# RLY.net
KiCad netlist of a schematic drawn in Altium Designer
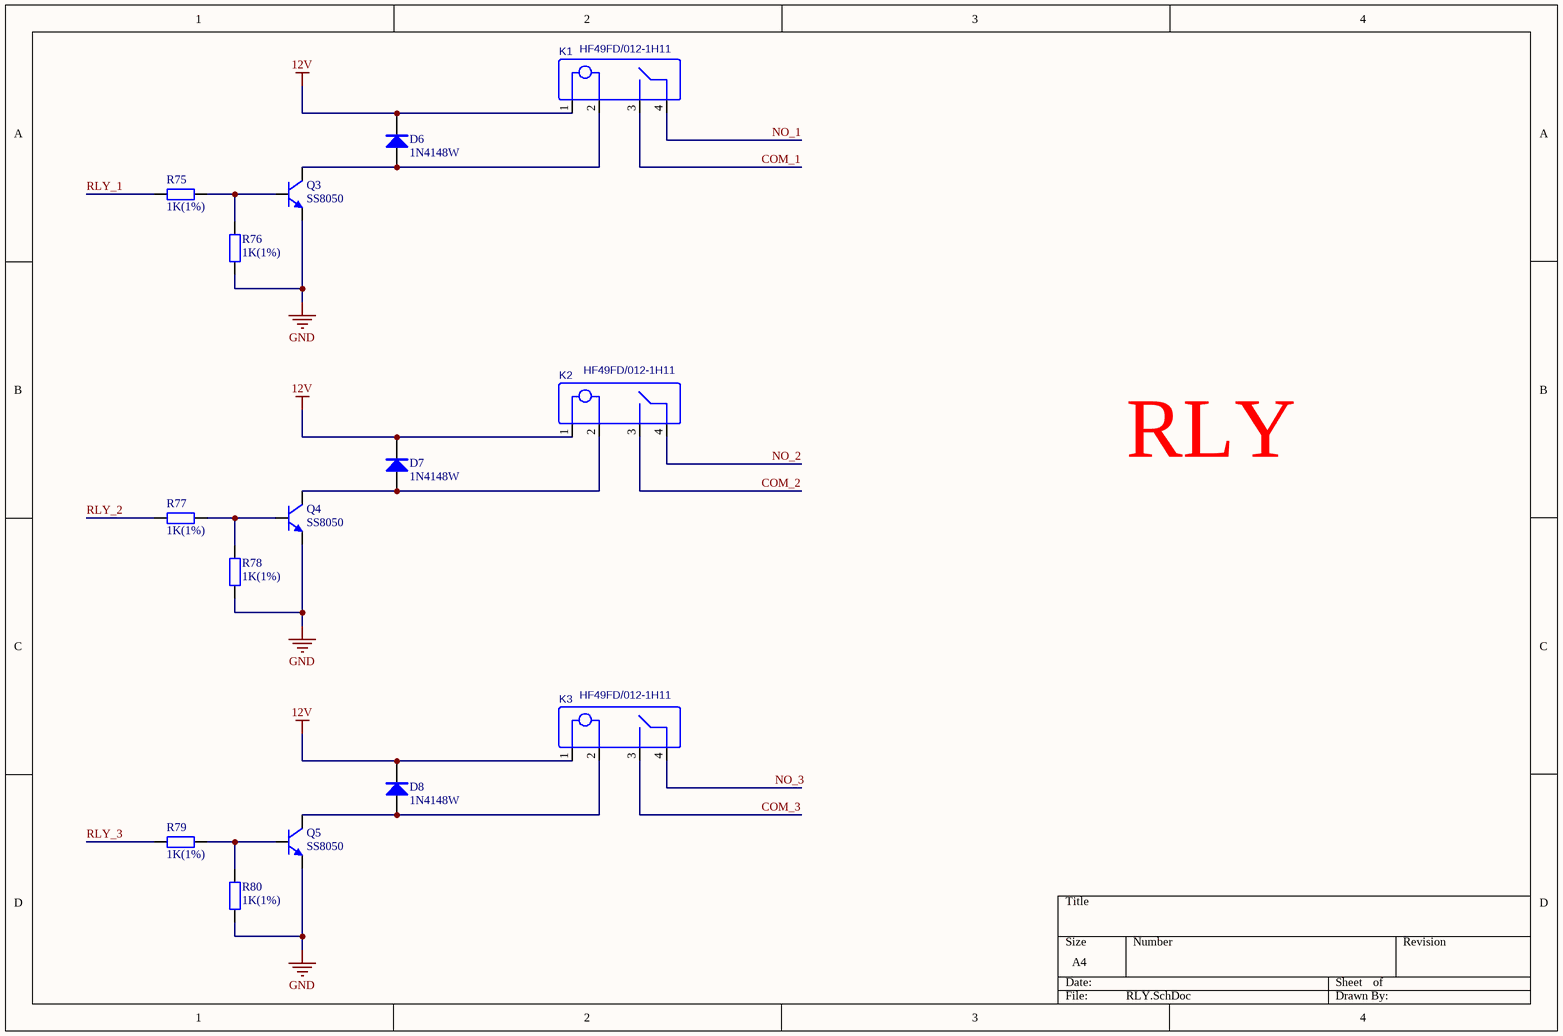
[diagram p0: RLY.SchDoc]

(export (version "E")
  (design (tool "Eeschema 10.0.6"))
  (components
    (comp (ref "D6")
      (value "1N4148W")
      (footprint "SOD-123")
      (description "高速开关二极管")
      (fields (field (name "版权归属") "源创客"))
      (libsource (lib "二极管-整流桥") (part "1N4148"))
    )
    (comp (ref "D7")
      (value "1N4148W")
      (footprint "SOD-123")
      (description "高速开关二极管")
      (fields (field (name "版权归属") "源创客"))
      (libsource (lib "二极管-整流桥") (part "1N4148"))
    )
    (comp (ref "D8")
      (value "1N4148W")
      (footprint "SOD-123")
      (description "高速开关二极管")
      (fields (field (name "版权归属") "源创客"))
      (libsource (lib "二极管-整流桥") (part "1N4148"))
    )
    (comp (ref "K1")
      (value "HF49FD/012-1H11")
      (footprint "RELAY-TH_HF49FD-XXX-1H11-XXX")
      (fields
        (field (name "BOM_SUPPLIER PART") "C399491")
        (field (name "BOM_MANUFACTURER PART") "HF49FD/012-1H12")
        (field (name "CONTRIBUTOR") "LCSC")
      )
      (libsource (lib "MICB") (part "HF49FD/012-1H11"))
    )
    (comp (ref "K2")
      (value "HF49FD/012-1H11")
      (footprint "RELAY-TH_HF49FD-XXX-1H11-XXX")
      (fields
        (field (name "BOM_SUPPLIER PART") "C399491")
        (field (name "BOM_MANUFACTURER PART") "HF49FD/012-1H12")
        (field (name "CONTRIBUTOR") "LCSC")
      )
      (libsource (lib "MICB") (part "HF49FD/012-1H11"))
    )
    (comp (ref "K3")
      (value "HF49FD/012-1H11")
      (footprint "RELAY-TH_HF49FD-XXX-1H11-XXX")
      (fields
        (field (name "BOM_SUPPLIER PART") "C399491")
        (field (name "BOM_MANUFACTURER PART") "HF49FD/012-1H12")
        (field (name "CONTRIBUTOR") "LCSC")
      )
      (libsource (lib "MICB") (part "HF49FD/012-1H11"))
    )
    (comp (ref "Q3")
      (value "SS8050")
      (footprint "SOT23-3N")
      (description "高频放大-NPN型")
      (fields (field (name "版权归属") "源创客"))
      (libsource (lib "三极管") (part "8050-SMD"))
    )
    (comp (ref "Q4")
      (value "SS8050")
      (footprint "SOT23-3N")
      (description "高频放大-NPN型")
      (fields (field (name "版权归属") "源创客"))
      (libsource (lib "三极管") (part "8050-SMD"))
    )
    (comp (ref "Q5")
      (value "SS8050")
      (footprint "SOT23-3N")
      (description "高频放大-NPN型")
      (fields (field (name "版权归属") "源创客"))
      (libsource (lib "三极管") (part "8050-SMD"))
    )
    (comp (ref "R75")
      (value "1K(1%)")
      (footprint "R 0603_L")
      (description "贴片电阻")
      (fields (field (name "版权归属") "源创客"))
      (libsource (lib "电阻-电容-电感") (part "R"))
    )
    (comp (ref "R76")
      (value "1K(1%)")
      (footprint "R 0603_L")
      (description "贴片电阻")
      (fields (field (name "版权归属") "源创客"))
      (libsource (lib "电阻-电容-电感") (part "R"))
    )
    (comp (ref "R77")
      (value "1K(1%)")
      (footprint "R 0603_L")
      (description "贴片电阻")
      (fields (field (name "版权归属") "源创客"))
      (libsource (lib "电阻-电容-电感") (part "R"))
    )
    (comp (ref "R78")
      (value "1K(1%)")
      (footprint "R 0603_L")
      (description "贴片电阻")
      (fields (field (name "版权归属") "源创客"))
      (libsource (lib "电阻-电容-电感") (part "R"))
    )
    (comp (ref "R79")
      (value "1K(1%)")
      (footprint "R 0603_L")
      (description "贴片电阻")
      (fields (field (name "版权归属") "源创客"))
      (libsource (lib "电阻-电容-电感") (part "R"))
    )
    (comp (ref "R80")
      (value "1K(1%)")
      (footprint "R 0603_L")
      (description "贴片电阻")
      (fields (field (name "版权归属") "源创客"))
      (libsource (lib "电阻-电容-电感") (part "R"))
    )
  )
  (nets
    (net (code "1") (name "/COM_1") (class "Default")
      (node (ref "K1") (pin "3") (pinfunction "3_3") (pintype "passive"))
    )
    (net (code "2") (name "/COM_2") (class "Default")
      (node (ref "K2") (pin "3") (pinfunction "3_3") (pintype "passive"))
    )
    (net (code "3") (name "/COM_3") (class "Default")
      (node (ref "K3") (pin "3") (pinfunction "3_3") (pintype "passive"))
    )
    (net (code "4") (name "/NO_1") (class "Default")
      (node (ref "K1") (pin "4") (pinfunction "4_4") (pintype "passive"))
    )
    (net (code "5") (name "/NO_2") (class "Default")
      (node (ref "K2") (pin "4") (pinfunction "4_4") (pintype "passive"))
    )
    (net (code "6") (name "/NO_3") (class "Default")
      (node (ref "K3") (pin "4") (pinfunction "4_4") (pintype "passive"))
    )
    (net (code "7") (name "/RLY_1") (class "Default")
      (node (ref "R75") (pin "2") (pinfunction "2_2") (pintype "passive"))
    )
    (net (code "8") (name "/RLY_2") (class "Default")
      (node (ref "R77") (pin "2") (pinfunction "2_2") (pintype "passive"))
    )
    (net (code "9") (name "/RLY_3") (class "Default")
      (node (ref "R79") (pin "2") (pinfunction "2_2") (pintype "passive"))
    )
    (net (code "10") (name "12V") (class "Default")
      (node (ref "D6") (pin "2") (pinfunction "K_2") (pintype "passive"))
      (node (ref "D7") (pin "2") (pinfunction "K_2") (pintype "passive"))
      (node (ref "D8") (pin "2") (pinfunction "K_2") (pintype "passive"))
      (node (ref "K1") (pin "1") (pinfunction "1_1") (pintype "passive"))
      (node (ref "K2") (pin "1") (pinfunction "1_1") (pintype "passive"))
      (node (ref "K3") (pin "1") (pinfunction "1_1") (pintype "passive"))
    )
    (net (code "11") (name "GND") (class "Default")
      (node (ref "Q3") (pin "2") (pinfunction "E_2") (pintype "passive"))
      (node (ref "Q4") (pin "2") (pinfunction "E_2") (pintype "passive"))
      (node (ref "Q5") (pin "2") (pinfunction "E_2") (pintype "passive"))
      (node (ref "R76") (pin "1") (pinfunction "1_1") (pintype "passive"))
      (node (ref "R78") (pin "1") (pinfunction "1_1") (pintype "passive"))
      (node (ref "R80") (pin "1") (pinfunction "1_1") (pintype "passive"))
    )
    (net (code "12") (name "Net-(D6-A)") (class "Default")
      (node (ref "D6") (pin "1") (pinfunction "A_1") (pintype "passive"))
      (node (ref "K1") (pin "2") (pinfunction "2_2") (pintype "passive"))
      (node (ref "Q3") (pin "3") (pinfunction "C_3") (pintype "passive"))
    )
    (net (code "13") (name "Net-(D7-A)") (class "Default")
      (node (ref "D7") (pin "1") (pinfunction "A_1") (pintype "passive"))
      (node (ref "K2") (pin "2") (pinfunction "2_2") (pintype "passive"))
      (node (ref "Q4") (pin "3") (pinfunction "C_3") (pintype "passive"))
    )
    (net (code "14") (name "Net-(D8-A)") (class "Default")
      (node (ref "D8") (pin "1") (pinfunction "A_1") (pintype "passive"))
      (node (ref "K3") (pin "2") (pinfunction "2_2") (pintype "passive"))
      (node (ref "Q5") (pin "3") (pinfunction "C_3") (pintype "passive"))
    )
    (net (code "15") (name "Net-(Q3-B)") (class "Default")
      (node (ref "Q3") (pin "1") (pinfunction "B_1") (pintype "passive"))
      (node (ref "R75") (pin "1") (pinfunction "1_1") (pintype "passive"))
      (node (ref "R76") (pin "2") (pinfunction "2_2") (pintype "passive"))
    )
    (net (code "16") (name "Net-(Q4-B)") (class "Default")
      (node (ref "Q4") (pin "1") (pinfunction "B_1") (pintype "passive"))
      (node (ref "R77") (pin "1") (pinfunction "1_1") (pintype "passive"))
      (node (ref "R78") (pin "2") (pinfunction "2_2") (pintype "passive"))
    )
    (net (code "17") (name "Net-(Q5-B)") (class "Default")
      (node (ref "Q5") (pin "1") (pinfunction "B_1") (pintype "passive"))
      (node (ref "R79") (pin "1") (pinfunction "1_1") (pintype "passive"))
      (node (ref "R80") (pin "2") (pinfunction "2_2") (pintype "passive"))
    )
  )
)
